# Sheet1.net
KiCad netlist of a schematic drawn in Altium Designer
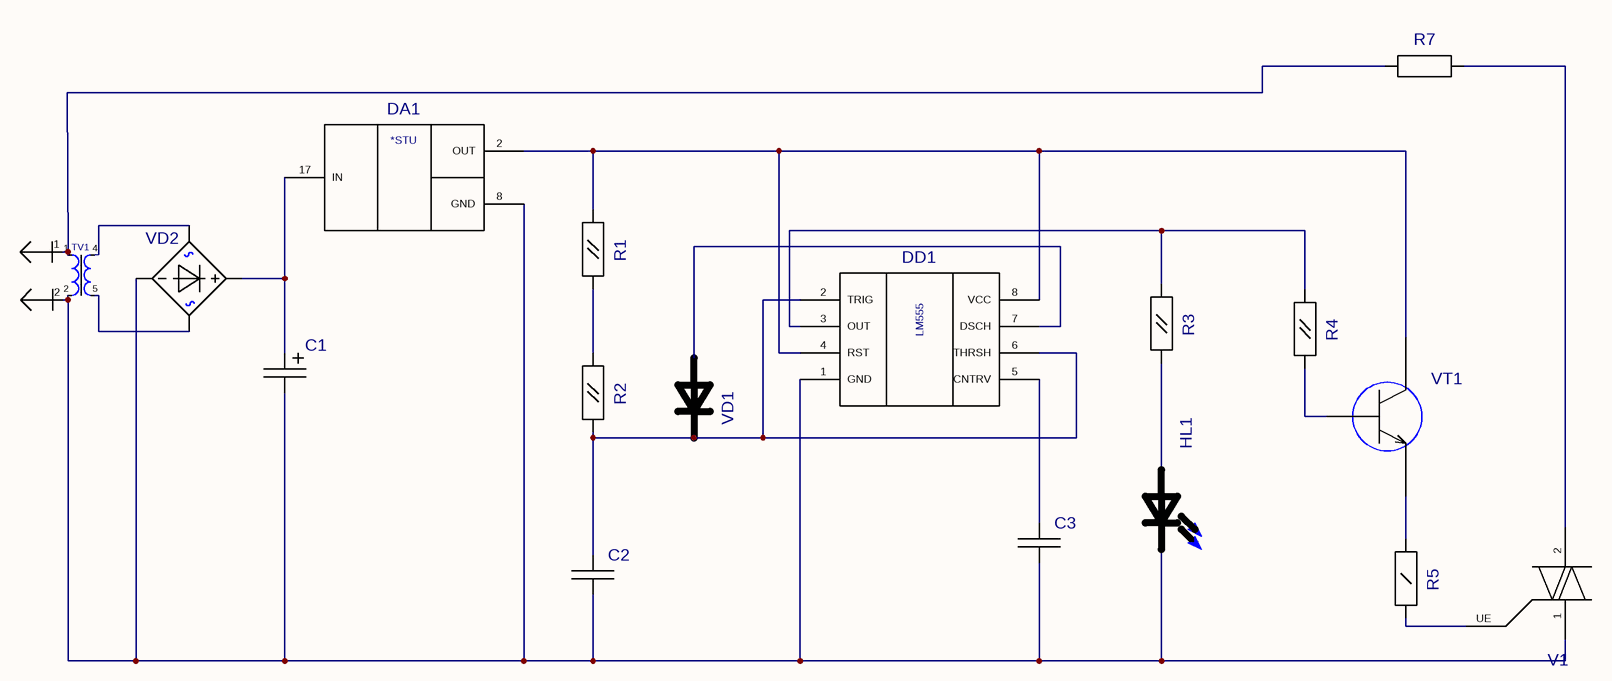
[diagram p0: Sheet1.SCHDOC]

(export (version "E")
  (design (tool "Eeschema 10.0.6"))
  (components
    (comp (ref "C1") (value "K534A-4") (footprint "K534A-4") (libsource (lib "*") (part "K534A-4")))
    (comp (ref "C2") (value "CC1812") (footprint "CC1812") (libsource (lib "*") (part "CC1812")))
    (comp (ref "C3") (value "CC1812") (footprint "CC1812") (libsource (lib "*") (part "CC1812")))
    (comp (ref "DA1")
      (value "КР142ЕН5А")
      (footprint "TO-220-KT-28-2")
      (libsource (lib "*") (part "КР142ЕН5А"))
    )
    (comp (ref "DD1") (value "LM555CM") (footprint "SO-8") (libsource (lib "*") (part "LM555CM")))
    (comp (ref "HL1") (value "3528") (footprint "3528") (libsource (lib "*") (part "3528")))
    (comp (ref "R1")
      (value "C2-33H-0.125W_OLD_UGO")
      (footprint "C2-33H-0.125W")
      (fields (field (name "AUTOR") "pcbdesigner.ru"))
      (libsource (lib "*") (part "C2-33H-0.125W_OLD_UGO"))
    )
    (comp (ref "R2")
      (value "C2-33H-0.125W_OLD_UGO")
      (footprint "C2-33H-0.125W")
      (fields (field (name "AUTOR") "pcbdesigner.ru"))
      (libsource (lib "*") (part "C2-33H-0.125W_OLD_UGO"))
    )
    (comp (ref "R3")
      (value "C2-33H-0.125W_OLD_UGO")
      (footprint "C2-33H-0.125W")
      (fields (field (name "AUTOR") "pcbdesigner.ru"))
      (libsource (lib "*") (part "C2-33H-0.125W_OLD_UGO"))
    )
    (comp (ref "R4")
      (value "C2-33H-0.125W_OLD_UGO")
      (footprint "C2-33H-0.125W")
      (fields (field (name "AUTOR") "pcbdesigner.ru"))
      (libsource (lib "*") (part "C2-33H-0.125W_OLD_UGO"))
    )
    (comp (ref "R5")
      (value "C2-33H-0.25W_OLD_UGO")
      (footprint "C2-33H-0.25W")
      (fields (field (name "AUTOR") "pcbdesigner.ru"))
      (libsource (lib "*") (part "C2-33H-0.25W_OLD_UGO"))
    )
    (comp (ref "R7")
      (value "C2-33Н-0.125W_10ММ")
      (footprint "C2-33H-0.125W_10MM")
      (libsource (lib "*") (part "C2-33Н-0.125W_10ММ"))
    )
    (comp (ref "TV1") (value "A1401") (footprint "TRS-3-1") (libsource (lib "*") (part "A1401")))
    (comp (ref "V1") (value "TC122") (footprint "TC122") (libsource (lib "*") (part "TC122")))
    (comp (ref "VD1") (value "1N34") (footprint "DO-7") (libsource (lib "*") (part "1N34")))
    (comp (ref "VD2") (value "RS402L") (footprint "RS-4L") (libsource (lib "*") (part "RS402L")))
    (comp (ref "VT1") (value "2N5551S") (footprint "SOT-23") (libsource (lib "*") (part "2N5551S")))
    (comp (ref "X1") (value "CAN9V-1") (footprint "CAN9V") (libsource (lib "*") (part "CAN9V-1")))
  )
  (nets
    (net (code "1") (name "Net-(C1-I{slash}OA)") (class "Default")
      (node (ref "C1") (pin "1") (pinfunction "I/OA_1") (pintype "passive"))
      (node (ref "DA1") (pin "17") (pinfunction "IN_17") (pintype "passive"))
      (node (ref "VD2") (pin "1") (pinfunction "+_1") (pintype "passive"))
    )
    (net (code "2") (name "Net-(C1-I{slash}OB)") (class "Default")
      (node (ref "C1") (pin "2") (pinfunction "I/OB_2") (pintype "passive"))
      (node (ref "C2") (pin "2") (pinfunction "2_2") (pintype "passive"))
      (node (ref "C3") (pin "2") (pinfunction "2_2") (pintype "passive"))
      (node (ref "DA1") (pin "8") (pinfunction "GND_8") (pintype "passive"))
      (node (ref "DD1") (pin "1") (pinfunction "GND_1") (pintype "passive"))
      (node (ref "HL1") (pin "K") (pinfunction "K_K") (pintype "passive"))
      (node (ref "TV1") (pin "2") (pintype "passive"))
      (node (ref "V1") (pin "1") (pinfunction "E2_1") (pintype "passive"))
      (node (ref "VD2") (pin "4") (pinfunction "-_4") (pintype "passive"))
      (node (ref "X1") (pin "2") (pinfunction "i/o_2") (pintype "passive"))
    )
    (net (code "3") (name "Net-(DA1-OUT)") (class "Default")
      (node (ref "DA1") (pin "2") (pinfunction "OUT_2") (pintype "passive"))
      (node (ref "DD1") (pin "4") (pinfunction "RST_4") (pintype "passive"))
      (node (ref "DD1") (pin "8") (pinfunction "VCC_8") (pintype "passive"))
      (node (ref "R1") (pin "1") (pinfunction "1_1") (pintype "passive"))
      (node (ref "VT1") (pin "3") (pinfunction "K_3") (pintype "passive"))
    )
    (net (code "4") (name "Net-(DD1-CNTRV)") (class "Default")
      (node (ref "C3") (pin "1") (pinfunction "1_1") (pintype "passive"))
      (node (ref "DD1") (pin "5") (pinfunction "CNTRV_5") (pintype "passive"))
    )
    (net (code "5") (name "Net-(DD1-DSCH)") (class "Default")
      (node (ref "DD1") (pin "7") (pinfunction "DSCH_7") (pintype "passive"))
      (node (ref "VD1") (pin "A") (pinfunction "A_A") (pintype "passive"))
    )
    (net (code "6") (name "Net-(DD1-OUT)") (class "Default")
      (node (ref "DD1") (pin "3") (pinfunction "OUT_3") (pintype "passive"))
      (node (ref "R3") (pin "1") (pinfunction "1_1") (pintype "passive"))
      (node (ref "R4") (pin "1") (pinfunction "1_1") (pintype "passive"))
    )
    (net (code "7") (name "Net-(DD1-THRSH)") (class "Default")
      (node (ref "C2") (pin "1") (pinfunction "1_1") (pintype "passive"))
      (node (ref "DD1") (pin "2") (pinfunction "TRIG_2") (pintype "passive"))
      (node (ref "DD1") (pin "6") (pinfunction "THRSH_6") (pintype "passive"))
      (node (ref "R2") (pin "2") (pinfunction "2_2") (pintype "passive"))
      (node (ref "VD1") (pin "K") (pinfunction "K_K") (pintype "passive"))
    )
    (net (code "8") (name "Net-(HL1-PadA)") (class "Default")
      (node (ref "HL1") (pin "A") (pinfunction "A_A") (pintype "passive"))
      (node (ref "R3") (pin "2") (pinfunction "2_2") (pintype "passive"))
    )
    (net (code "9") (name "Net-(R1-Pad2)") (class "Default")
      (node (ref "R1") (pin "2") (pinfunction "2_2") (pintype "passive"))
      (node (ref "R2") (pin "1") (pinfunction "1_1") (pintype "passive"))
    )
    (net (code "10") (name "Net-(R5-Pad2)") (class "Default")
      (node (ref "R5") (pin "2") (pinfunction "2_2") (pintype "passive"))
      (node (ref "V1") (pin "UE") (pinfunction "UE_UE") (pintype "passive"))
    )
    (net (code "11") (name "Net-(TV1-Pad4)") (class "Default")
      (node (ref "TV1") (pin "4") (pintype "passive"))
      (node (ref "VD2") (pin "2") (pintype "passive"))
    )
    (net (code "12") (name "Net-(TV1-Pad5)") (class "Default")
      (node (ref "TV1") (pin "5") (pintype "passive"))
      (node (ref "VD2") (pin "3") (pintype "passive"))
    )
    (net (code "13") (name "Net-(V1-E1)") (class "Default")
      (node (ref "R7") (pin "2") (pinfunction "2_2") (pintype "passive"))
      (node (ref "V1") (pin "2") (pinfunction "E1_2") (pintype "passive"))
    )
    (net (code "14") (name "Net-(VT1-B)") (class "Default")
      (node (ref "R4") (pin "2") (pinfunction "2_2") (pintype "passive"))
      (node (ref "VT1") (pin "2") (pinfunction "B_2") (pintype "passive"))
    )
    (net (code "15") (name "Net-(VT1-E)") (class "Default")
      (node (ref "R5") (pin "1") (pinfunction "1_1") (pintype "passive"))
      (node (ref "VT1") (pin "1") (pinfunction "E_1") (pintype "passive"))
    )
    (net (code "16") (name "Net-(X1A-i{slash}o)") (class "Default")
      (node (ref "R7") (pin "1") (pinfunction "1_1") (pintype "passive"))
      (node (ref "TV1") (pin "1") (pintype "passive"))
      (node (ref "X1") (pin "1") (pinfunction "i/o_1") (pintype "passive"))
    )
    (net (code "17") (name "unconnected-(DA1-Pad4)") (class "Default")
      (node (ref "DA1") (pin "4") (pintype "passive"))
    )
    (net (code "18") (name "unconnected-(TV1-Pad3)") (class "Default")
      (node (ref "TV1") (pin "3") (pintype "passive"))
    )
    (net (code "19") (name "unconnected-(TV1-Pad6)") (class "Default")
      (node (ref "TV1") (pin "6") (pintype "passive"))
    )
    (net (code "20") (name "unconnected-(TV1-Pad7)") (class "Default")
      (node (ref "TV1") (pin "7") (pintype "passive"))
    )
    (net (code "21") (name "unconnected-(TV1-Pad8)") (class "Default")
      (node (ref "TV1") (pin "8") (pintype "passive"))
    )
    (net (code "22") (name "unconnected-(V1-Pad4)") (class "Default")
      (node (ref "V1") (pin "4") (pintype "passive"))
    )
    (net (code "23") (name "unconnected-(V1-Pad5)") (class "Default")
      (node (ref "V1") (pin "5") (pintype "passive"))
    )
  )
)
